# TSAL_Board_B.net
KiCad netlist of a schematic drawn in Altium Designer
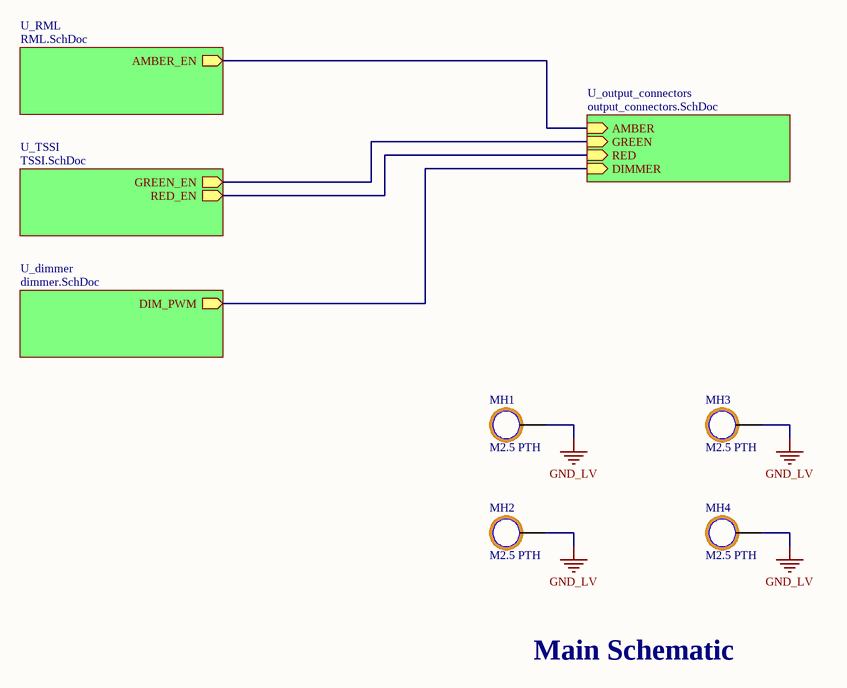
[diagram p0: TSAL_Board_B.SchDoc]

(export (version "E")
  (design (tool "Eeschema 10.0.6"))
  (components
    (comp (ref "MH1")
      (value "M2.5 PTH")
      (footprint "MH__M2_5")
      (libsource (lib "Ontario Tech Racing New") (part "MH__PTH__MOUNTING_HOLE_NO_BOM"))
    )
    (comp (ref "MH2")
      (value "M2.5 PTH")
      (footprint "MH__M2_5")
      (libsource (lib "Ontario Tech Racing New") (part "MH__PTH__MOUNTING_HOLE_NO_BOM"))
    )
    (comp (ref "MH3")
      (value "M2.5 PTH")
      (footprint "MH__M2_5")
      (libsource (lib "Ontario Tech Racing New") (part "MH__PTH__MOUNTING_HOLE_NO_BOM"))
    )
    (comp (ref "MH4")
      (value "M2.5 PTH")
      (footprint "MH__M2_5")
      (libsource (lib "Ontario Tech Racing New") (part "MH__PTH__MOUNTING_HOLE_NO_BOM"))
    )
  )
  (nets
    (net (code "5") (name "GND_LV") (class "Default")
      (node (ref "MH1") (pin "1") (pinfunction "1_1") (pintype "passive"))
      (node (ref "MH2") (pin "1") (pinfunction "1_1") (pintype "passive"))
      (node (ref "MH3") (pin "1") (pinfunction "1_1") (pintype "passive"))
      (node (ref "MH4") (pin "1") (pinfunction "1_1") (pintype "passive"))
    )
  )
)
